# E-Reader_v110.net
KiCad netlist of a schematic drawn in EAGLE
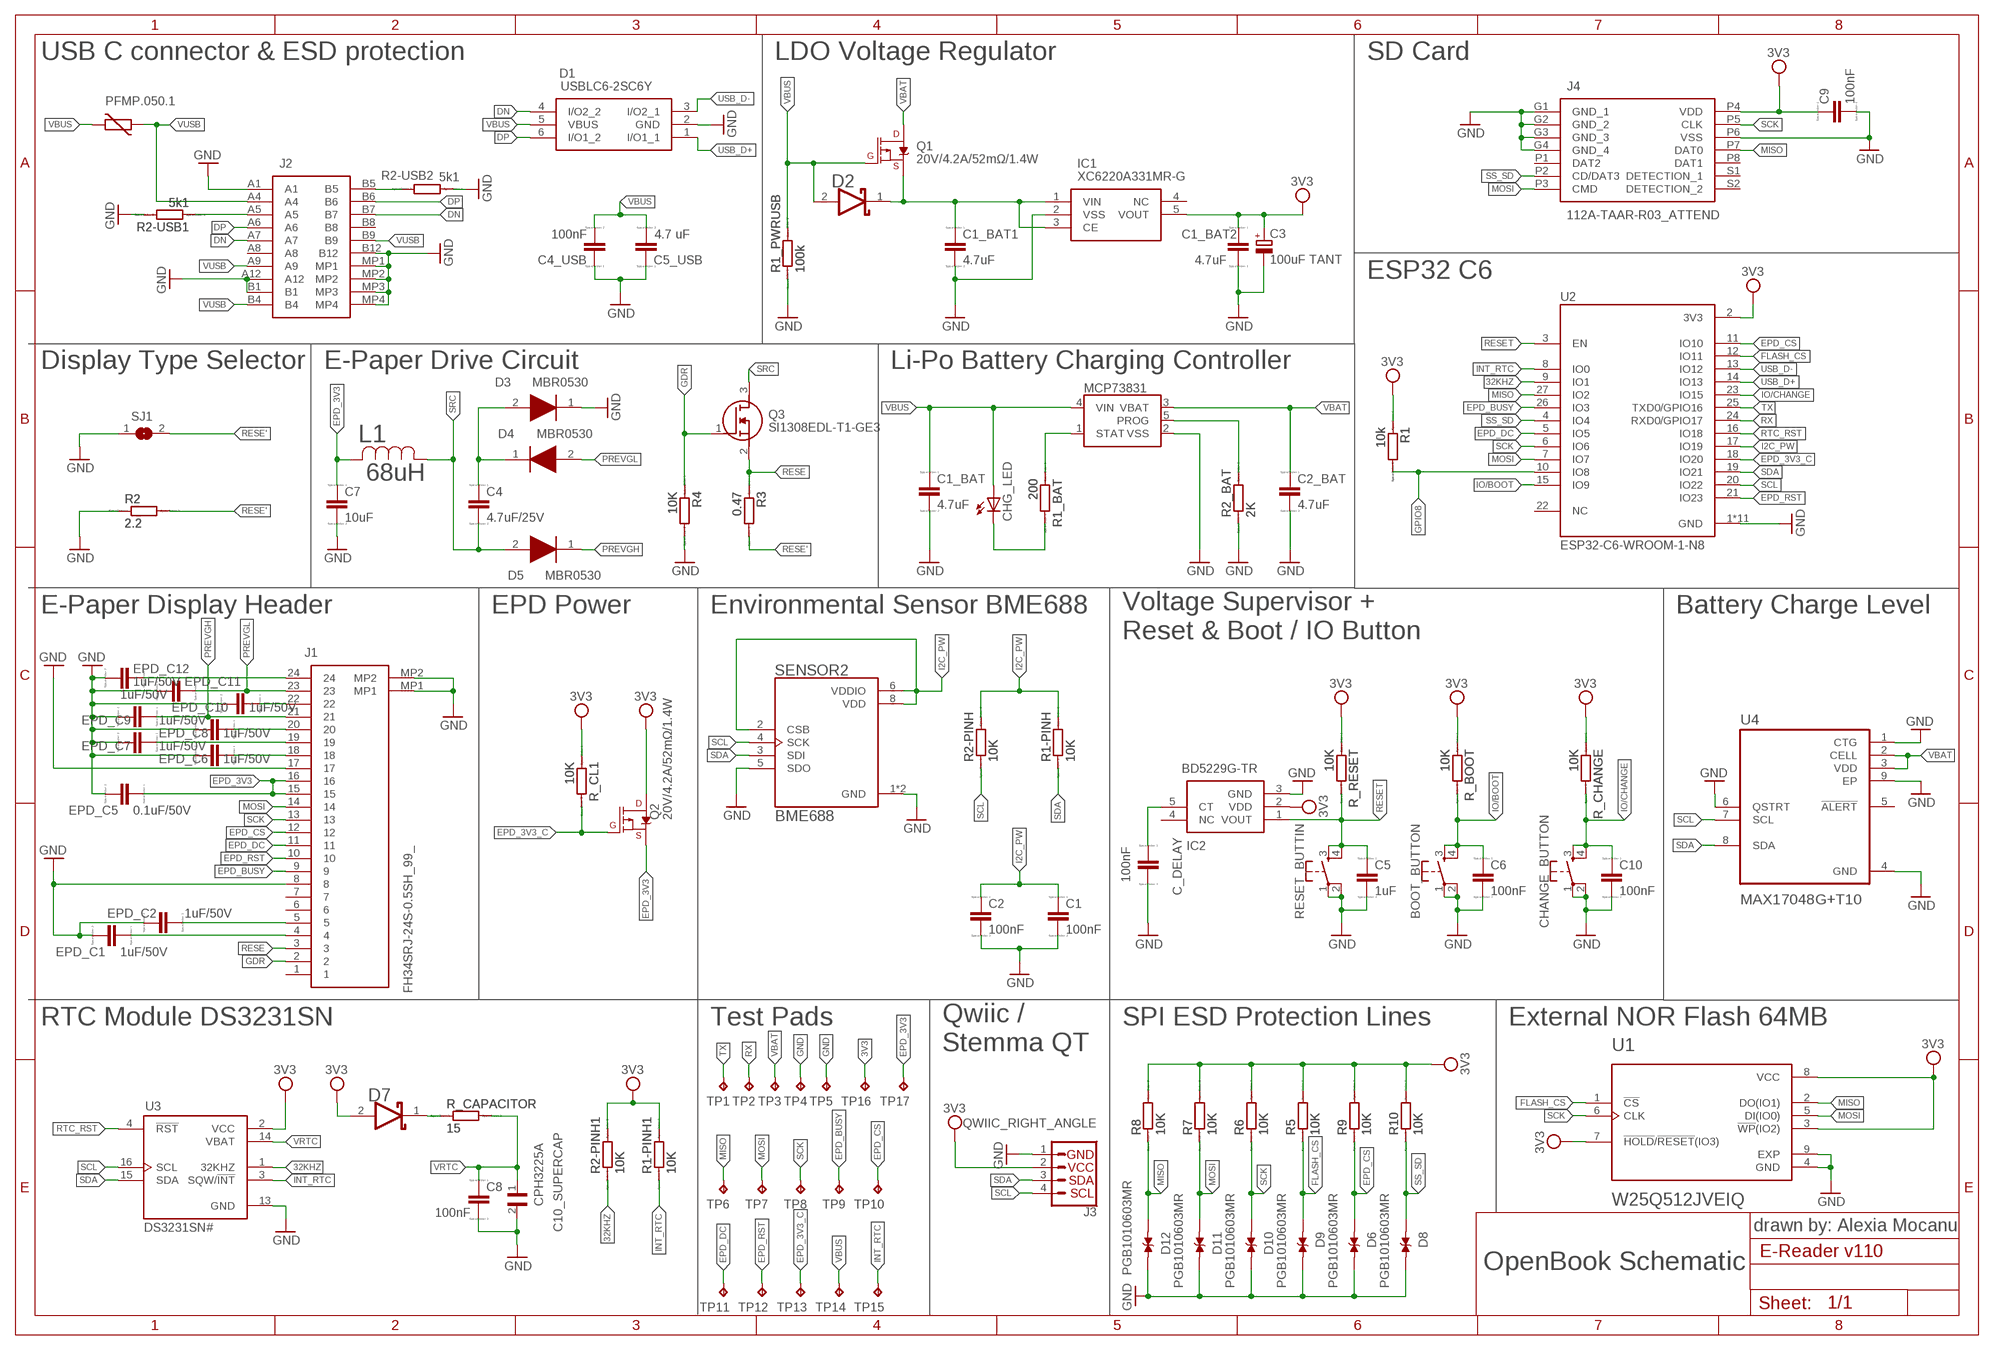
[diagram p0: schematic, sheet 1]

(export (version "E")
  (design (tool "Eeschema 10.0.6"))
  (components
    (comp (ref "BOOT_BUTTON")
      (value "BUTTON_CUSYOMV1")
      (footprint "eagle-import:MYBUTTON")
      (libsource (lib "eagle-import") (part "BUTTON_CUSYOMV1"))
    )
    (comp (ref "C1")
      (value "100nF")
      (footprint "eagle-import:EAGLE-LTSPICE_C0402")
      (libsource (lib "eagle-import") (part "EAGLE-LTSPICE_CC0402"))
    )
    (comp (ref "C1_BAT")
      (value "4.7uF")
      (footprint "eagle-import:EAGLE-LTSPICE_C0402")
      (libsource (lib "eagle-import") (part "EAGLE-LTSPICE_CC0402"))
    )
    (comp (ref "C1_BAT1")
      (value "4.7uF")
      (footprint "eagle-import:EAGLE-LTSPICE_C0402")
      (libsource (lib "eagle-import") (part "EAGLE-LTSPICE_CC0402"))
    )
    (comp (ref "C1_BAT2")
      (value "4.7uF")
      (footprint "eagle-import:EAGLE-LTSPICE_C0402")
      (libsource (lib "eagle-import") (part "EAGLE-LTSPICE_CC0402"))
    )
    (comp (ref "C2")
      (value "100nF")
      (footprint "eagle-import:EAGLE-LTSPICE_C0402")
      (libsource (lib "eagle-import") (part "EAGLE-LTSPICE_CC0402"))
    )
    (comp (ref "C2_BAT")
      (value "4.7uF")
      (footprint "eagle-import:EAGLE-LTSPICE_C0402")
      (libsource (lib "eagle-import") (part "EAGLE-LTSPICE_CC0402"))
    )
    (comp (ref "C3")
      (value "100uF TANT")
      (footprint "eagle-import:RCL_CT3528")
      (libsource (lib "eagle-import") (part "RCL_CPOL-EUCT3528"))
    )
    (comp (ref "C4")
      (value "4.7uF/25V")
      (footprint "eagle-import:EAGLE-LTSPICE_C0402")
      (libsource (lib "eagle-import") (part "EAGLE-LTSPICE_CC0402"))
    )
    (comp (ref "C4_USB")
      (value "100nF")
      (footprint "eagle-import:EAGLE-LTSPICE_C0402")
      (libsource (lib "eagle-import") (part "EAGLE-LTSPICE_CC0402"))
    )
    (comp (ref "C5")
      (value "1uF")
      (footprint "eagle-import:EAGLE-LTSPICE_C0402")
      (libsource (lib "eagle-import") (part "EAGLE-LTSPICE_CC0402"))
    )
    (comp (ref "C5_USB")
      (value "4.7 uF")
      (footprint "eagle-import:EAGLE-LTSPICE_C0402")
      (libsource (lib "eagle-import") (part "EAGLE-LTSPICE_CC0402"))
    )
    (comp (ref "C6")
      (value "100nF")
      (footprint "eagle-import:EAGLE-LTSPICE_C0402")
      (libsource (lib "eagle-import") (part "EAGLE-LTSPICE_CC0402"))
    )
    (comp (ref "C7")
      (value "10uF")
      (footprint "eagle-import:EAGLE-LTSPICE_C0402")
      (libsource (lib "eagle-import") (part "EAGLE-LTSPICE_CC0402"))
    )
    (comp (ref "C8")
      (value "100nF")
      (footprint "eagle-import:EAGLE-LTSPICE_C0402")
      (libsource (lib "eagle-import") (part "EAGLE-LTSPICE_CC0402"))
    )
    (comp (ref "C9")
      (value "100nF")
      (footprint "eagle-import:EAGLE-LTSPICE_C0402")
      (libsource (lib "eagle-import") (part "EAGLE-LTSPICE_CC0402"))
    )
    (comp (ref "C10")
      (value "100nF")
      (footprint "eagle-import:EAGLE-LTSPICE_C0402")
      (libsource (lib "eagle-import") (part "EAGLE-LTSPICE_CC0402"))
    )
    (comp (ref "C10_SUPERCAP")
      (value "CPH3225A")
      (footprint "eagle-import:CAPCP3225X100N")
      (fields (field (name "MF") "Seiko Instruments"))
      (libsource (lib "eagle-import") (part "CPH3225A"))
    )
    (comp (ref "CHANGE_BUTTON")
      (value "BUTTON_CUSYOMV1")
      (footprint "eagle-import:MYBUTTON")
      (libsource (lib "eagle-import") (part "BUTTON_CUSYOMV1"))
    )
    (comp (ref "CHG_LED")
      (value "ADAFRUIT_LEDCHIP-LED0603")
      (footprint "eagle-import:ADAFRUIT_CHIP-LED0603")
      (libsource (lib "eagle-import") (part "ADAFRUIT_LEDCHIP-LED0603"))
    )
    (comp (ref "C_DELAY")
      (value "100nF")
      (footprint "eagle-import:EAGLE-LTSPICE_C0402")
      (libsource (lib "eagle-import") (part "EAGLE-LTSPICE_CC0402"))
    )
    (comp (ref "D1")
      (value "USBLC6-2SC6Y")
      (footprint "eagle-import:SOT95P280X145-6N")
      (fields (field (name "MF") "STMicroelectronics"))
      (libsource (lib "eagle-import") (part "USBLC6-2SC6Y"))
    )
    (comp (ref "D2")
      (value "ESP32_WROVER_AVX---SD0805S020S1R0_AVX_SD0805S020S1R0_0_0AVX_SD0805S020S1R0_0_0")
      (footprint "eagle-import:ESP32_WROVER_AVX---SD0805S020S1R0_AVX_SD0805S020S1R0_0")
      (fields
        (field (name "DIGIKEY_PART_NUMBER") "478-7800-1-ND")
        (field (name "MF") "AVX")
        (field (name "MOUSER_PART_NUMBER") "581-SD0805S020S1R0")
      )
      (libsource (lib "eagle-import") (part "ESP32_WROVER_AVX---SD0805S020S1R0_AVX_SD0805S020S1R0_0_0AVX_SD0805S020S1R0_0_0"))
    )
    (comp (ref "D3")
      (value "MBR0530")
      (footprint "eagle-import:SOD3716X135N")
      (fields (field (name "MF") "ON Semiconductor"))
      (libsource (lib "eagle-import") (part "MBR0530"))
    )
    (comp (ref "D4")
      (value "MBR0530")
      (footprint "eagle-import:SOD3716X135N")
      (fields (field (name "MF") "ON Semiconductor"))
      (libsource (lib "eagle-import") (part "MBR0530"))
    )
    (comp (ref "D5")
      (value "MBR0530")
      (footprint "eagle-import:SOD3716X135N")
      (fields (field (name "MF") "ON Semiconductor"))
      (libsource (lib "eagle-import") (part "MBR0530"))
    )
    (comp (ref "D6")
      (value "PGB1010603MR")
      (footprint "eagle-import:DIOC1608X36N")
      (fields (field (name "MF") "Littelfuse Inc."))
      (libsource (lib "eagle-import") (part "PGB1010603MR"))
    )
    (comp (ref "D7")
      (value "SD0805S020S1R0")
      (footprint "eagle-import:ESP32_WROVER_AVX---SD0805S020S1R0_AVX_SD0805S020S1R0_0")
      (fields
        (field (name "DIGIKEY_PART_NUMBER") "478-7800-1-ND")
        (field (name "MF") "AVX")
        (field (name "MOUSER_PART_NUMBER") "581-SD0805S020S1R0")
      )
      (libsource (lib "eagle-import") (part "ESP32_WROVER_AVX---SD0805S020S1R0_AVX_SD0805S020S1R0_0_0AVX_SD0805S020S1R0_0_0"))
    )
    (comp (ref "D8")
      (value "PGB1010603MR")
      (footprint "eagle-import:DIOC1608X36N")
      (fields (field (name "MF") "Littelfuse Inc."))
      (libsource (lib "eagle-import") (part "PGB1010603MR"))
    )
    (comp (ref "D9")
      (value "PGB1010603MR")
      (footprint "eagle-import:DIOC1608X36N")
      (fields (field (name "MF") "Littelfuse Inc."))
      (libsource (lib "eagle-import") (part "PGB1010603MR"))
    )
    (comp (ref "D10")
      (value "PGB1010603MR")
      (footprint "eagle-import:DIOC1608X36N")
      (fields (field (name "MF") "Littelfuse Inc."))
      (libsource (lib "eagle-import") (part "PGB1010603MR"))
    )
    (comp (ref "D11")
      (value "PGB1010603MR")
      (footprint "eagle-import:DIOC1608X36N")
      (fields (field (name "MF") "Littelfuse Inc."))
      (libsource (lib "eagle-import") (part "PGB1010603MR"))
    )
    (comp (ref "D12")
      (value "PGB1010603MR")
      (footprint "eagle-import:DIOC1608X36N")
      (fields (field (name "MF") "Littelfuse Inc."))
      (libsource (lib "eagle-import") (part "PGB1010603MR"))
    )
    (comp (ref "EPD_C1")
      (value "1uF/50V")
      (footprint "eagle-import:EAGLE-LTSPICE_C0402")
      (libsource (lib "eagle-import") (part "EAGLE-LTSPICE_CC0402"))
    )
    (comp (ref "EPD_C2")
      (value "1uF/50V")
      (footprint "eagle-import:EAGLE-LTSPICE_C0402")
      (libsource (lib "eagle-import") (part "EAGLE-LTSPICE_CC0402"))
    )
    (comp (ref "EPD_C5")
      (value "0.1uF/50V")
      (footprint "eagle-import:EAGLE-LTSPICE_C0402")
      (libsource (lib "eagle-import") (part "EAGLE-LTSPICE_CC0402"))
    )
    (comp (ref "EPD_C6")
      (value "1uF/50V")
      (footprint "eagle-import:EAGLE-LTSPICE_C0402")
      (libsource (lib "eagle-import") (part "EAGLE-LTSPICE_CC0402"))
    )
    (comp (ref "EPD_C7")
      (value "1uF/50V")
      (footprint "eagle-import:EAGLE-LTSPICE_C0402")
      (libsource (lib "eagle-import") (part "EAGLE-LTSPICE_CC0402"))
    )
    (comp (ref "EPD_C8")
      (value "1uF/50V")
      (footprint "eagle-import:EAGLE-LTSPICE_C0402")
      (libsource (lib "eagle-import") (part "EAGLE-LTSPICE_CC0402"))
    )
    (comp (ref "EPD_C9")
      (value "1uF/50V")
      (footprint "eagle-import:EAGLE-LTSPICE_C0402")
      (libsource (lib "eagle-import") (part "EAGLE-LTSPICE_CC0402"))
    )
    (comp (ref "EPD_C10")
      (value "1uF/50V")
      (footprint "eagle-import:EAGLE-LTSPICE_C0402")
      (libsource (lib "eagle-import") (part "EAGLE-LTSPICE_CC0402"))
    )
    (comp (ref "EPD_C11")
      (value "1uF/50V")
      (footprint "eagle-import:EAGLE-LTSPICE_C0402")
      (libsource (lib "eagle-import") (part "EAGLE-LTSPICE_CC0402"))
    )
    (comp (ref "EPD_C12")
      (value "1uF/50V")
      (footprint "eagle-import:EAGLE-LTSPICE_C0402")
      (libsource (lib "eagle-import") (part "EAGLE-LTSPICE_CC0402"))
    )
    (comp (ref "IC1")
      (value "XC6220A331MR-G")
      (footprint "eagle-import:SOT95P280X120-5N")
      (fields (field (name "MOUSER_PART_NUMBER") "865-XC6220A331MR-G"))
      (libsource (lib "eagle-import") (part "XC6220A331MR-G"))
    )
    (comp (ref "IC2")
      (value "BD5229G-TR")
      (footprint "eagle-import:SOT95P280X125-5N")
      (fields (field (name "MOUSER_PART_NUMBER") "755-BD5229G-TR"))
      (libsource (lib "eagle-import") (part "BD5229G-TR"))
    )
    (comp (ref "J1")
      (value "FH34SRJ-24S-0.5SH_99_")
      (footprint "eagle-import:FH34SRJ24S05SH99")
      (fields
        (field (name "MANUFACTURER_PART_NUMBER") "FH34SRJ-24S-0.5SH(99)")
        (field (name "MOUSER_PART_NUMBER") "798-FH34SRJ24S05SH99")
      )
      (libsource (lib "eagle-import") (part "FH34SRJ-24S-0.5SH_99_"))
    )
    (comp (ref "J2")
      (value "SAMACSYS_PARTS_USB4110-GF-A")
      (footprint "eagle-import:SAMACSYS_PARTS_USB4110GFA")
      (fields
        (field (name "MANUFACTURER_PART_NUMBER") "USB4110-GF-A")
        (field (name "MOUSER_PART_NUMBER") "640-USB4110-GF-A")
      )
      (libsource (lib "eagle-import") (part "SAMACSYS_PARTS_USB4110-GF-A"))
    )
    (comp (ref "J3")
      (value "QWIIC_RIGHT_ANGLE")
      (footprint "eagle-import:JST04_1MM_RA")
      (libsource (lib "eagle-import") (part "QWIIC_CONNECTORJS-1MM"))
    )
    (comp (ref "J4")
      (value "112A-TAAR-R03_ATTEND")
      (footprint "eagle-import:112ATAARR03ATTEND")
      (fields (field (name "MANUFACTURER_PART_NUMBER") "112A-TAAR-R03 ATTEND"))
      (libsource (lib "eagle-import") (part "112A-TAAR-R03_ATTEND"))
    )
    (comp (ref "L1")
      (value "68uH")
      (footprint "eagle-import:IND_4828-WE-TPC_WRE")
      (fields
        (field (name "MANUFACTURER_PART_NUMBER") "744043680")
        (field (name "COPYRIGHT") "Copyright (C) 2024 Ultra Librarian. All rights reserved.")
      )
      (libsource (lib "eagle-import") (part "744043680IND_4828-WE-TPC_WRE"))
    )
    (comp (ref "MCP73831")
      (value "ESP32_WROVER_SPARKFUN-IC-POWER_MCP73831")
      (footprint "eagle-import:ESP32_WROVER_SPARKFUN-IC-POWER_SOT23-5")
      (libsource (lib "eagle-import") (part "ESP32_WROVER_SPARKFUN-IC-POWER_MCP73831"))
    )
    (comp (ref "PFMP.050.1")
      (value "ESP32C6_VARISTORCN1812")
      (footprint "eagle-import:ESP32C6_VARISTOR_CT_CN1812")
      (libsource (lib "eagle-import") (part "ESP32C6_VARISTORCN1812"))
    )
    (comp (ref "Q1")
      (value "20V/4.2A/52mΩ/1.4W")
      (footprint "eagle-import:ESP32_WROVER_SPARKFUN-DISCRETESEMI_SOT23-3")
      (libsource (lib "eagle-import") (part "ESP32_WROVER_SPARKFUN-DISCRETESEMI_MOSFET_PCH-DMG2305UX-7"))
    )
    (comp (ref "Q2")
      (value "20V/4.2A/52mΩ/1.4W")
      (footprint "eagle-import:ESP32_WROVER_SPARKFUN-DISCRETESEMI_SOT23-3")
      (fields (field (name "SPICEPREFIX") "Q"))
      (libsource (lib "eagle-import") (part "ESP32_WROVER_SPARKFUN-DISCRETESEMI_MOSFET_PCH-DMG2305UX-7"))
    )
    (comp (ref "Q3")
      (value "SI1308EDL-T1-GE3")
      (footprint "eagle-import:SOT65P210X110-3N")
      (fields (field (name "MF") "Vishay Siliconix"))
      (libsource (lib "eagle-import") (part "SI1308EDL-T1-GE3"))
    )
    (comp (ref "R1")
      (value "10k")
      (footprint "eagle-import:ESP32_WROVER_EAGLE-LTSPICE_R0402")
      (libsource (lib "eagle-import") (part "ESP32_WROVER_EAGLE-LTSPICE_RR0402"))
    )
    (comp (ref "R1-PINH")
      (value "10K")
      (footprint "eagle-import:ESP32_WROVER_EAGLE-LTSPICE_R0402")
      (libsource (lib "eagle-import") (part "ESP32_WROVER_EAGLE-LTSPICE_RR0402"))
    )
    (comp (ref "R1-PINH1")
      (value "10K")
      (footprint "eagle-import:ESP32_WROVER_EAGLE-LTSPICE_R0402")
      (libsource (lib "eagle-import") (part "ESP32_WROVER_EAGLE-LTSPICE_RR0402"))
    )
    (comp (ref "R1_BAT")
      (value "200")
      (footprint "eagle-import:ESP32_WROVER_EAGLE-LTSPICE_R0402")
      (libsource (lib "eagle-import") (part "ESP32_WROVER_EAGLE-LTSPICE_RR0402"))
    )
    (comp (ref "R1_PWRUSB")
      (value "100k")
      (footprint "eagle-import:ESP32_WROVER_EAGLE-LTSPICE_R0402")
      (libsource (lib "eagle-import") (part "ESP32_WROVER_EAGLE-LTSPICE_RR0402"))
    )
    (comp (ref "R2")
      (value "2.2")
      (footprint "eagle-import:ESP32_WROVER_EAGLE-LTSPICE_R0402")
      (libsource (lib "eagle-import") (part "ESP32_WROVER_EAGLE-LTSPICE_RR0402"))
    )
    (comp (ref "R2-PINH")
      (value "10K")
      (footprint "eagle-import:ESP32_WROVER_EAGLE-LTSPICE_R0402")
      (libsource (lib "eagle-import") (part "ESP32_WROVER_EAGLE-LTSPICE_RR0402"))
    )
    (comp (ref "R2-PINH1")
      (value "10K")
      (footprint "eagle-import:ESP32_WROVER_EAGLE-LTSPICE_R0402")
      (libsource (lib "eagle-import") (part "ESP32_WROVER_EAGLE-LTSPICE_RR0402"))
    )
    (comp (ref "R2-USB1")
      (value "5k1")
      (footprint "eagle-import:ESP32_WROVER_EAGLE-LTSPICE_R0402")
      (libsource (lib "eagle-import") (part "ESP32_WROVER_EAGLE-LTSPICE_RR0402"))
    )
    (comp (ref "R2-USB2")
      (value "5k1")
      (footprint "eagle-import:ESP32_WROVER_EAGLE-LTSPICE_R0402")
      (libsource (lib "eagle-import") (part "ESP32_WROVER_EAGLE-LTSPICE_RR0402"))
    )
    (comp (ref "R2_BAT")
      (value "2K")
      (footprint "eagle-import:ESP32_WROVER_EAGLE-LTSPICE_R0402")
      (libsource (lib "eagle-import") (part "ESP32_WROVER_EAGLE-LTSPICE_RR0402"))
    )
    (comp (ref "R3")
      (value "0.47")
      (footprint "eagle-import:ESP32_WROVER_EAGLE-LTSPICE_R0402")
      (libsource (lib "eagle-import") (part "ESP32_WROVER_EAGLE-LTSPICE_RR0402"))
    )
    (comp (ref "R4")
      (value "10K")
      (footprint "eagle-import:ESP32_WROVER_EAGLE-LTSPICE_R0402")
      (libsource (lib "eagle-import") (part "ESP32_WROVER_EAGLE-LTSPICE_RR0402"))
    )
    (comp (ref "R5")
      (value "10K")
      (footprint "eagle-import:ESP32_WROVER_EAGLE-LTSPICE_R0402")
      (libsource (lib "eagle-import") (part "ESP32_WROVER_EAGLE-LTSPICE_RR0402"))
    )
    (comp (ref "R6")
      (value "10K")
      (footprint "eagle-import:ESP32_WROVER_EAGLE-LTSPICE_R0402")
      (libsource (lib "eagle-import") (part "ESP32_WROVER_EAGLE-LTSPICE_RR0402"))
    )
    (comp (ref "R7")
      (value "10K")
      (footprint "eagle-import:ESP32_WROVER_EAGLE-LTSPICE_R0402")
      (libsource (lib "eagle-import") (part "ESP32_WROVER_EAGLE-LTSPICE_RR0402"))
    )
    (comp (ref "R8")
      (value "10K")
      (footprint "eagle-import:ESP32_WROVER_EAGLE-LTSPICE_R0402")
      (libsource (lib "eagle-import") (part "ESP32_WROVER_EAGLE-LTSPICE_RR0402"))
    )
    (comp (ref "R9")
      (value "10K")
      (footprint "eagle-import:ESP32_WROVER_EAGLE-LTSPICE_R0402")
      (libsource (lib "eagle-import") (part "ESP32_WROVER_EAGLE-LTSPICE_RR0402"))
    )
    (comp (ref "R10")
      (value "10K")
      (footprint "eagle-import:ESP32_WROVER_EAGLE-LTSPICE_R0402")
      (libsource (lib "eagle-import") (part "ESP32_WROVER_EAGLE-LTSPICE_RR0402"))
    )
    (comp (ref "RESET_BUTTIN")
      (value "BUTTON_CUSYOMV1")
      (footprint "eagle-import:MYBUTTON")
      (libsource (lib "eagle-import") (part "BUTTON_CUSYOMV1"))
    )
    (comp (ref "R_BOOT")
      (value "10K")
      (footprint "eagle-import:ESP32_WROVER_EAGLE-LTSPICE_R0402")
      (libsource (lib "eagle-import") (part "ESP32_WROVER_EAGLE-LTSPICE_RR0402"))
    )
    (comp (ref "R_CAPACITOR")
      (value "15")
      (footprint "eagle-import:ESP32_WROVER_EAGLE-LTSPICE_R0402")
      (libsource (lib "eagle-import") (part "ESP32_WROVER_EAGLE-LTSPICE_RR0402"))
    )
    (comp (ref "R_CHANGE")
      (value "10K")
      (footprint "eagle-import:ESP32_WROVER_EAGLE-LTSPICE_R0402")
      (libsource (lib "eagle-import") (part "ESP32_WROVER_EAGLE-LTSPICE_RR0402"))
    )
    (comp (ref "R_CL1")
      (value "10K")
      (footprint "eagle-import:ESP32_WROVER_EAGLE-LTSPICE_R0402")
      (libsource (lib "eagle-import") (part "ESP32_WROVER_EAGLE-LTSPICE_RR0402"))
    )
    (comp (ref "R_RESET")
      (value "10K")
      (footprint "eagle-import:ESP32_WROVER_EAGLE-LTSPICE_R0402")
      (libsource (lib "eagle-import") (part "ESP32_WROVER_EAGLE-LTSPICE_RR0402"))
    )
    (comp (ref "SENSOR2")
      (value "BME688")
      (footprint "eagle-import:ESP32_WROVER_BME680_PSON80P300X300X100-8N")
      (fields (field (name "MF") "Bosch Sensortec") (field (name "MP") "BME680"))
      (libsource (lib "eagle-import") (part "ESP32_WROVER_BME680_BME680"))
    )
    (comp (ref "SJ1") (value "SJ") (footprint "eagle-import:SJ") (libsource (lib "eagle-import") (part "SJ")))
    (comp (ref "TP1")
      (value "TPTP20R")
      (footprint "eagle-import:TP20R")
      (libsource (lib "eagle-import") (part "TPTP20R"))
    )
    (comp (ref "TP2")
      (value "TPTP20R")
      (footprint "eagle-import:TP20R")
      (libsource (lib "eagle-import") (part "TPTP20R"))
    )
    (comp (ref "TP3")
      (value "TPTP20R")
      (footprint "eagle-import:TP20R")
      (libsource (lib "eagle-import") (part "TPTP20R"))
    )
    (comp (ref "TP4")
      (value "TPTP20R")
      (footprint "eagle-import:TP20R")
      (libsource (lib "eagle-import") (part "TPTP20R"))
    )
    (comp (ref "TP5")
      (value "TPTP20R")
      (footprint "eagle-import:TP20R")
      (libsource (lib "eagle-import") (part "TPTP20R"))
    )
    (comp (ref "TP6")
      (value "TPTP20R")
      (footprint "eagle-import:TP20R")
      (libsource (lib "eagle-import") (part "TPTP20R"))
    )
    (comp (ref "TP7")
      (value "TPTP20R")
      (footprint "eagle-import:TP20R")
      (libsource (lib "eagle-import") (part "TPTP20R"))
    )
    (comp (ref "TP8")
      (value "TPTP20R")
      (footprint "eagle-import:TP20R")
      (libsource (lib "eagle-import") (part "TPTP20R"))
    )
    (comp (ref "TP9")
      (value "TPTP20R")
      (footprint "eagle-import:TP20R")
      (libsource (lib "eagle-import") (part "TPTP20R"))
    )
    (comp (ref "TP10")
      (value "TPTP20R")
      (footprint "eagle-import:TP20R")
      (libsource (lib "eagle-import") (part "TPTP20R"))
    )
    (comp (ref "TP11")
      (value "TPTP20R")
      (footprint "eagle-import:TP20R")
      (libsource (lib "eagle-import") (part "TPTP20R"))
    )
    (comp (ref "TP12")
      (value "TPTP20R")
      (footprint "eagle-import:TP20R")
      (libsource (lib "eagle-import") (part "TPTP20R"))
    )
    (comp (ref "TP13")
      (value "TPTP20R")
      (footprint "eagle-import:TP20R")
      (libsource (lib "eagle-import") (part "TPTP20R"))
    )
    (comp (ref "TP14")
      (value "TPTP20R")
      (footprint "eagle-import:TP20R")
      (libsource (lib "eagle-import") (part "TPTP20R"))
    )
    (comp (ref "TP15")
      (value "TPTP20R")
      (footprint "eagle-import:TP20R")
      (libsource (lib "eagle-import") (part "TPTP20R"))
    )
    (comp (ref "TP16")
      (value "TPTP20R")
      (footprint "eagle-import:TP20R")
      (libsource (lib "eagle-import") (part "TPTP20R"))
    )
    (comp (ref "TP17")
      (value "TPTP20R")
      (footprint "eagle-import:TP20R")
      (libsource (lib "eagle-import") (part "TPTP20R"))
    )
    (comp (ref "U1")
      (value "W25Q512JVEIQ")
      (footprint "eagle-import:SON127P600X800X80-9N")
      (fields (field (name "MF") "Winbond Electronics"))
      (libsource (lib "eagle-import") (part "W25Q512JVEIQ"))
    )
    (comp (ref "U2")
      (value "ESP32-C6-WROOM-1-N8")
      (footprint "eagle-import:XCVR_ESP32-C6-WROOM-1-N8")
      (fields (field (name "MF") "Espressif Systems"))
      (libsource (lib "eagle-import") (part "ESP32-C6-WROOM-1-N8"))
    )
    (comp (ref "U3")
      (value "DS3231SN#")
      (footprint "eagle-import:SOIC127P1032X265-16N")
      (fields (field (name "MF") "Analog Devices"))
      (libsource (lib "eagle-import") (part "DS3231SN#"))
    )
    (comp (ref "U4")
      (value "MAX17048G+T10")
      (footprint "eagle-import:SON50P200X200X80-9N")
      (fields (field (name "MF") "Analog Devices"))
      (libsource (lib "eagle-import") (part "MAX17048G+T10"))
    )
  )
  (nets
    (net (code "1") (name "3V3") (class "Default")
      (node (ref "C1_BAT2") (pin "1") (pinfunction "1_1") (pintype "passive"))
      (node (ref "C3") (pin "+") (pinfunction "+_+") (pintype "passive"))
      (node (ref "C9") (pin "1") (pinfunction "1_1") (pintype "passive"))
      (node (ref "D7") (pin "2") (pinfunction "ANODE_2") (pintype "bidirectional"))
      (node (ref "IC1") (pin "5") (pinfunction "VOUT_5") (pintype "bidirectional"))
      (node (ref "IC2") (pin "2") (pinfunction "VDD_2") (pintype "bidirectional"))
      (node (ref "J3") (pin "2") (pinfunction "2_2") (pintype "power_in"))
      (node (ref "J4") (pin "P4") (pinfunction "VDD_P4") (pintype "bidirectional"))
      (node (ref "Q2") (pin "3") (pinfunction "D_3") (pintype "bidirectional"))
      (node (ref "R1") (pin "1") (pinfunction "1_1") (pintype "passive"))
      (node (ref "R1-PINH1") (pin "2") (pinfunction "2_2") (pintype "passive"))
      (node (ref "R10") (pin "2") (pinfunction "2_2") (pintype "passive"))
      (node (ref "R2-PINH1") (pin "2") (pinfunction "2_2") (pintype "passive"))
      (node (ref "R5") (pin "2") (pinfunction "2_2") (pintype "passive"))
      (node (ref "R6") (pin "2") (pinfunction "2_2") (pintype "passive"))
      (node (ref "R7") (pin "2") (pinfunction "2_2") (pintype "passive"))
      (node (ref "R8") (pin "2") (pinfunction "2_2") (pintype "passive"))
      (node (ref "R9") (pin "2") (pinfunction "2_2") (pintype "passive"))
      (node (ref "R_BOOT") (pin "1") (pinfunction "1_1") (pintype "passive"))
      (node (ref "R_CHANGE") (pin "1") (pinfunction "1_1") (pintype "passive"))
      (node (ref "R_CL1") (pin "1") (pinfunction "1_1") (pintype "passive"))
      (node (ref "R_RESET") (pin "1") (pinfunction "1_1") (pintype "passive"))
      (node (ref "TP16") (pin "TP") (pinfunction "TP_TP") (pintype "input"))
      (node (ref "U1") (pin "3") (pinfunction "~{WP}(IO2)_3") (pintype "bidirectional"))
      (node (ref "U1") (pin "7") (pinfunction "~{HOLD}/~{RESET}(IO3)_7") (pintype "bidirectional"))
      (node (ref "U1") (pin "8") (pinfunction "VCC_8") (pintype "power_in"))
      (node (ref "U2") (pin "2") (pinfunction "3V3_2") (pintype "power_in"))
      (node (ref "U3") (pin "2") (pinfunction "VCC_2") (pintype "power_in"))
    )
    (net (code "2") (name "32KHZ") (class "Default")
      (node (ref "R2-PINH1") (pin "1") (pinfunction "1_1") (pintype "passive"))
      (node (ref "U2") (pin "9") (pinfunction "IO1_9") (pintype "bidirectional"))
      (node (ref "U3") (pin "1") (pinfunction "32KHZ_1") (pintype "output"))
    )
    (net (code "3") (name "DN") (class "Default")
      (node (ref "D1") (pin "4") (pinfunction "I/O2_2_4") (pintype "bidirectional"))
      (node (ref "J2") (pin "A7") (pinfunction "A7_A7") (pintype "bidirectional"))
      (node (ref "J2") (pin "B7") (pinfunction "B7_B7") (pintype "bidirectional"))
    )
    (net (code "4") (name "DP") (class "Default")
      (node (ref "D1") (pin "6") (pinfunction "I/O1_2_6") (pintype "bidirectional"))
      (node (ref "J2") (pin "A6") (pinfunction "A6_A6") (pintype "bidirectional"))
      (node (ref "J2") (pin "B6") (pinfunction "B6_B6") (pintype "bidirectional"))
    )
    (net (code "5") (name "EPD_3V3") (class "Default")
      (node (ref "C7") (pin "1") (pinfunction "1_1") (pintype "passive"))
      (node (ref "EPD_C5") (pin "1") (pinfunction "1_1") (pintype "passive"))
      (node (ref "J1") (pin "15") (pinfunction "15_15") (pintype "bidirectional"))
      (node (ref "J1") (pin "16") (pinfunction "16_16") (pintype "bidirectional"))
      (node (ref "L1") (pin "2") (pinfunction "2_2") (pintype "passive"))
      (node (ref "Q2") (pin "2") (pinfunction "S_2") (pintype "bidirectional"))
      (node (ref "TP17") (pin "TP") (pinfunction "TP_TP") (pintype "input"))
    )
    (net (code "6") (name "EPD_3V3_C") (class "Default")
      (node (ref "Q2") (pin "1") (pinfunction "G_1") (pintype "bidirectional"))
      (node (ref "R_CL1") (pin "2") (pinfunction "2_2") (pintype "passive"))
      (node (ref "TP13") (pin "TP") (pinfunction "TP_TP") (pintype "input"))
      (node (ref "U2") (pin "18") (pinfunction "IO20_18") (pintype "bidirectional"))
    )
    (net (code "7") (name "EPD_BUSY") (class "Default")
      (node (ref "J1") (pin "9") (pinfunction "9_9") (pintype "bidirectional"))
      (node (ref "TP9") (pin "TP") (pinfunction "TP_TP") (pintype "input"))
      (node (ref "U2") (pin "26") (pinfunction "IO3_26") (pintype "bidirectional"))
    )
    (net (code "8") (name "EPD_CS") (class "Default")
      (node (ref "D6") (pin "1") (pinfunction "1_1") (pintype "passive"))
      (node (ref "J1") (pin "12") (pinfunction "12_12") (pintype "bidirectional"))
      (node (ref "R9") (pin "1") (pinfunction "1_1") (pintype "passive"))
      (node (ref "TP10") (pin "TP") (pinfunction "TP_TP") (pintype "input"))
      (node (ref "U2") (pin "11") (pinfunction "IO10_11") (pintype "bidirectional"))
    )
    (net (code "9") (name "EPD_DC") (class "Default")
      (node (ref "J1") (pin "11") (pinfunction "11_11") (pintype "bidirectional"))
      (node (ref "TP11") (pin "TP") (pinfunction "TP_TP") (pintype "input"))
      (node (ref "U2") (pin "5") (pinfunction "IO5_5") (pintype "bidirectional"))
    )
    (net (code "10") (name "EPD_RST") (class "Default")
      (node (ref "J1") (pin "10") (pinfunction "10_10") (pintype "bidirectional"))
      (node (ref "TP12") (pin "TP") (pinfunction "TP_TP") (pintype "input"))
      (node (ref "U2") (pin "21") (pinfunction "IO23_21") (pintype "bidirectional"))
    )
    (net (code "11") (name "FLASH_CS") (class "Default")
      (node (ref "D9") (pin "1") (pinfunction "1_1") (pintype "passive"))
      (node (ref "R5") (pin "1") (pinfunction "1_1") (pintype "passive"))
      (node (ref "U1") (pin "1") (pinfunction "~{CS}_1") (pintype "input"))
      (node (ref "U2") (pin "12") (pinfunction "IO11_12") (pintype "bidirectional"))
    )
    (net (code "12") (name "GDR") (class "Default")
      (node (ref "J1") (pin "2") (pinfunction "2_2") (pintype "bidirectional"))
      (node (ref "Q3") (pin "1") (pinfunction "G_1") (pintype "bidirectional"))
      (node (ref "R4") (pin "1") (pinfunction "1_1") (pintype "passive"))
    )
    (net (code "13") (name "GND") (class "Default")
      (node (ref "BOOT_BUTTON") (pin "1") (pinfunction "1_1") (pintype "passive"))
      (node (ref "BOOT_BUTTON") (pin "2") (pinfunction "2_2") (pintype "passive"))
      (node (ref "C1") (pin "2") (pinfunction "2_2") (pintype "passive"))
      (node (ref "C10") (pin "2") (pinfunction "2_2") (pintype "passive"))
      (node (ref "C10_SUPERCAP") (pin "2") (pinfunction "2_2") (pintype "passive"))
      (node (ref "C1_BAT") (pin "2") (pinfunction "2_2") (pintype "passive"))
      (node (ref "C1_BAT1") (pin "2") (pinfunction "2_2") (pintype "passive"))
      (node (ref "C1_BAT2") (pin "2") (pinfunction "2_2") (pintype "passive"))
      (node (ref "C2") (pin "2") (pinfunction "2_2") (pintype "passive"))
      (node (ref "C2_BAT") (pin "2") (pinfunction "2_2") (pintype "passive"))
      (node (ref "C3") (pin "-") (pinfunction "-_-") (pintype "passive"))
      (node (ref "C4_USB") (pin "1") (pinfunction "1_1") (pintype "passive"))
      (node (ref "C5") (pin "2") (pinfunction "2_2") (pintype "passive"))
      (node (ref "C5_USB") (pin "1") (pinfunction "1_1") (pintype "passive"))
      (node (ref "C6") (pin "2") (pinfunction "2_2") (pintype "passive"))
      (node (ref "C7") (pin "2") (pinfunction "2_2") (pintype "passive"))
      (node (ref "C8") (pin "2") (pinfunction "2_2") (pintype "passive"))
      (node (ref "C9") (pin "2") (pinfunction "2_2") (pintype "passive"))
      (node (ref "CHANGE_BUTTON") (pin "1") (pinfunction "1_1") (pintype "passive"))
      (node (ref "CHANGE_BUTTON") (pin "2") (pinfunction "2_2") (pintype "passive"))
      (node (ref "C_DELAY") (pin "2") (pinfunction "2_2") (pintype "passive"))
      (node (ref "D1") (pin "2") (pinfunction "GND_2") (pintype "bidirectional"))
      (node (ref "D10") (pin "2") (pinfunction "2_2") (pintype "passive"))
      (node (ref "D11") (pin "2") (pinfunction "2_2") (pintype "passive"))
      (node (ref "D12") (pin "2") (pinfunction "2_2") (pintype "passive"))
      (node (ref "D3") (pin "1") (pinfunction "K_1") (pintype "bidirectional"))
      (node (ref "D6") (pin "2") (pinfunction "2_2") (pintype "passive"))
      (node (ref "D8") (pin "2") (pinfunction "2_2") (pintype "passive"))
      (node (ref "D9") (pin "2") (pinfunction "2_2") (pintype "passive"))
      (node (ref "EPD_C1") (pin "2") (pinfunction "2_2") (pintype "passive"))
      (node (ref "EPD_C10") (pin "2") (pinfunction "2_2") (pintype "passive"))
      (node (ref "EPD_C11") (pin "2") (pinfunction "2_2") (pintype "passive"))
      (node (ref "EPD_C12") (pin "2") (pinfunction "2_2") (pintype "passive"))
      (node (ref "EPD_C2") (pin "2") (pinfunction "2_2") (pintype "passive"))
      (node (ref "EPD_C5") (pin "2") (pinfunction "2_2") (pintype "passive"))
      (node (ref "EPD_C6") (pin "2") (pinfunction "2_2") (pintype "passive"))
      (node (ref "EPD_C7") (pin "2") (pinfunction "2_2") (pintype "passive"))
      (node (ref "EPD_C8") (pin "2") (pinfunction "2_2") (pintype "passive"))
      (node (ref "EPD_C9") (pin "2") (pinfunction "2_2") (pintype "passive"))
      (node (ref "IC1") (pin "2") (pinfunction "VSS_2") (pintype "bidirectional"))
      (node (ref "IC2") (pin "3") (pinfunction "GND_3") (pintype "bidirectional"))
      (node (ref "J1") (pin "17") (pinfunction "17_17") (pintype "bidirectional"))
      (node (ref "J1") (pin "8") (pinfunction "8_8") (pintype "bidirectional"))
      (node (ref "J1") (pin "MP1") (pinfunction "MP1_MP1") (pintype "bidirectional"))
      (node (ref "J1") (pin "MP2") (pinfunction "MP2_MP2") (pintype "bidirectional"))
      (node (ref "J2") (pin "A1") (pinfunction "A1_A1") (pintype "bidirectional"))
      (node (ref "J2") (pin "A12") (pinfunction "A12_A12") (pintype "bidirectional"))
      (node (ref "J2") (pin "B1") (pinfunction "B1_B1") (pintype "bidirectional"))
      (node (ref "J2") (pin "B12") (pinfunction "B12_B12") (pintype "bidirectional"))
      (node (ref "J2") (pin "MP1") (pinfunction "MP1_MP1") (pintype "bidirectional"))
      (node (ref "J2") (pin "MP2") (pinfunction "MP2_MP2") (pintype "bidirectional"))
      (node (ref "J2") (pin "MP3") (pinfunction "MP3_MP3") (pintype "bidirectional"))
      (node (ref "J2") (pin "MP4") (pinfunction "MP4_MP4") (pintype "bidirectional"))
      (node (ref "J3") (pin "1") (pinfunction "1_1") (pintype "power_in"))
      (node (ref "J4") (pin "G1") (pinfunction "GND_1_G1") (pintype "bidirectional"))
      (node (ref "J4") (pin "G2") (pinfunction "GND_2_G2") (pintype "bidirectional"))
      (node (ref "J4") (pin "G3") (pinfunction "GND_3_G3") (pintype "bidirectional"))
      (node (ref "J4") (pin "G4") (pinfunction "GND_4_G4") (pintype "bidirectional"))
      (node (ref "J4") (pin "P6") (pinfunction "VSS_P6") (pintype "bidirectional"))
      (node (ref "MCP73831") (pin "2") (pinfunction "VSS_2") (pintype "power_in"))
      (node (ref "R1_PWRUSB") (pin "1") (pinfunction "1_1") (pintype "passive"))
      (node (ref "R2") (pin "1") (pinfunction "1_1") (pintype "passive"))
      (node (ref "R2-USB1") (pin "2") (pinfunction "2_2") (pintype "passive"))
      (node (ref "R2-USB2") (pin "1") (pinfunction "1_1") (pintype "passive"))
      (node (ref "R2_BAT") (pin "1") (pinfunction "1_1") (pintype "passive"))
      (node (ref "R4") (pin "2") (pinfunction "2_2") (pintype "passive"))
      (node (ref "RESET_BUTTIN") (pin "1") (pinfunction "1_1") (pintype "passive"))
      (node (ref "RESET_BUTTIN") (pin "2") (pinfunction "2_2") (pintype "passive"))
      (node (ref "SENSOR2") (pin "1") (pinfunction "GND_1") (pintype "power_in"))
      (node (ref "SENSOR2") (pin "5") (pinfunction "SDO_5") (pintype "bidirectional"))
      (node (ref "SENSOR2") (pin "7") (pinfunction "GND_7") (pintype "power_in"))
      (node (ref "SJ1") (pin "1") (pinfunction "1_1") (pintype "passive"))
      (node (ref "TP4") (pin "TP") (pinfunction "TP_TP") (pintype "input"))
      (node (ref "TP5") (pin "TP") (pinfunction "TP_TP") (pintype "input"))
      (node (ref "U1") (pin "4") (pinfunction "GND_4") (pintype "power_in"))
      (node (ref "U1") (pin "9") (pinfunction "EXP_9") (pintype "passive"))
      (node (ref "U2") (pin "1") (pinfunction "GND_1") (pintype "power_in"))
      (node (ref "U2") (pin "28") (pinfunction "GND_28") (pintype "power_in"))
      (node (ref "U2") (pin "29_1") (pinfunction "GND_29_1") (pintype "power_in"))
      (node (ref "U2") (pin "29_2") (pinfunction "GND_29_2") (pintype "power_in"))
      (node (ref "U2") (pin "29_3") (pinfunction "GND_29_3") (pintype "power_in"))
      (node (ref "U2") (pin "29_4") (pinfunction "GND_29_4") (pintype "power_in"))
      (node (ref "U2") (pin "29_5") (pinfunction "GND_29_5") (pintype "power_in"))
      (node (ref "U2") (pin "29_6") (pinfunction "GND_29_6") (pintype "power_in"))
      (node (ref "U2") (pin "29_7") (pinfunction "GND_29_7") (pintype "power_in"))
      (node (ref "U2") (pin "29_8") (pinfunction "GND_29_8") (pintype "power_in"))
      (node (ref "U2") (pin "29_9") (pinfunction "GND_29_9") (pintype "power_in"))
      (node (ref "U3") (pin "13") (pinfunction "GND_13") (pintype "power_in"))
      (node (ref "U4") (pin "1") (pinfunction "CTG_1") (pintype "power_in"))
      (node (ref "U4") (pin "4") (pinfunction "GND_4") (pintype "power_in"))
      (node (ref "U4") (pin "6") (pinfunction "QSTRT_6") (pintype "input"))
      (node (ref "U4") (pin "9") (pinfunction "EP_9") (pintype "power_in"))
    )
    (net (code "14") (name "GPIO8") (class "Default")
      (node (ref "R1") (pin "2") (pinfunction "2_2") (pintype "passive"))
      (node (ref "U2") (pin "10") (pinfunction "IO8_10") (pintype "bidirectional"))
    )
    (net (code "15") (name "I2C_PW") (class "Default")
      (node (ref "C1") (pin "1") (pinfunction "1_1") (pintype "passive"))
      (node (ref "C2") (pin "1") (pinfunction "1_1") (pintype "passive"))
      (node (ref "R1-PINH") (pin "2") (pinfunction "2_2") (pintype "passive"))
      (node (ref "R2-PINH") (pin "2") (pinfunction "2_2") (pintype "passive"))
      (node (ref "SENSOR2") (pin "2") (pinfunction "CSB_2") (pintype "input"))
      (node (ref "SENSOR2") (pin "6") (pinfunction "VDDIO_6") (pintype "power_in"))
      (node (ref "SENSOR2") (pin "8") (pinfunction "VDD_8") (pintype "power_in"))
      (node (ref "U2") (pin "17") (pinfunction "IO19_17") (pintype "bidirectional"))
    )
    (net (code "16") (name "INT_RTC") (class "Default")
      (node (ref "R1-PINH1") (pin "1") (pinfunction "1_1") (pintype "passive"))
      (node (ref "TP15") (pin "TP") (pinfunction "TP_TP") (pintype "input"))
      (node (ref "U2") (pin "8") (pinfunction "IO0_8") (pintype "bidirectional"))
      (node (ref "U3") (pin "3") (pinfunction "SQW/~{INT}_3") (pintype "output"))
    )
    (net (code "17") (name "IO{slash}BOOT") (class "Default")
      (node (ref "BOOT_BUTTON") (pin "3") (pinfunction "3_3") (pintype "passive"))
      (node (ref "BOOT_BUTTON") (pin "4") (pinfunction "4_4") (pintype "passive"))
      (node (ref "C6") (pin "1") (pinfunction "1_1") (pintype "passive"))
      (node (ref "R_BOOT") (pin "2") (pinfunction "2_2") (pintype "passive"))
      (node (ref "U2") (pin "15") (pinfunction "IO9_15") (pintype "bidirectional"))
    )
    (net (code "18") (name "IO{slash}CHANGE") (class "Default")
      (node (ref "C10") (pin "1") (pinfunction "1_1") (pintype "passive"))
      (node (ref "CHANGE_BUTTON") (pin "3") (pinfunction "3_3") (pintype "passive"))
      (node (ref "CHANGE_BUTTON") (pin "4") (pinfunction "4_4") (pintype "passive"))
      (node (ref "R_CHANGE") (pin "2") (pinfunction "2_2") (pintype "passive"))
      (node (ref "U2") (pin "23") (pinfunction "IO15_23") (pintype "bidirectional"))
    )
    (net (code "19") (name "MISO") (class "Default")
      (node (ref "D12") (pin "1") (pinfunction "1_1") (pintype "passive"))
      (node (ref "J4") (pin "P7") (pinfunction "DAT0_P7") (pintype "bidirectional"))
      (node (ref "R8") (pin "1") (pinfunction "1_1") (pintype "passive"))
      (node (ref "TP6") (pin "TP") (pinfunction "TP_TP") (pintype "input"))
      (node (ref "U1") (pin "2") (pinfunction "DO(IO1)_2") (pintype "bidirectional"))
      (node (ref "U2") (pin "27") (pinfunction "IO2_27") (pintype "bidirectional"))
    )
    (net (code "20") (name "MOSI") (class "Default")
      (node (ref "D11") (pin "1") (pinfunction "1_1") (pintype "passive"))
      (node (ref "J1") (pin "14") (pinfunction "14_14") (pintype "bidirectional"))
      (node (ref "J4") (pin "P3") (pinfunction "CMD_P3") (pintype "bidirectional"))
      (node (ref "R7") (pin "1") (pinfunction "1_1") (pintype "passive"))
      (node (ref "TP7") (pin "TP") (pinfunction "TP_TP") (pintype "input"))
      (node (ref "U1") (pin "5") (pinfunction "DI(IO0)_5") (pintype "bidirectional"))
      (node (ref "U2") (pin "7") (pinfunction "IO7_7") (pintype "bidirectional"))
    )
    (net (code "21") (name "Net-(CHG_LED-PadC)") (class "Default")
      (node (ref "CHG_LED") (pin "C") (pinfunction "C_C") (pintype "passive"))
      (node (ref "R1_BAT") (pin "2") (pinfunction "2_2") (pintype "passive"))
    )
    (net (code "22") (name "Net-(D2-CATHODE)") (class "Default")
      (node (ref "C1_BAT1") (pin "1") (pinfunction "1_1") (pintype "passive"))
      (node (ref "D2") (pin "1") (pinfunction "CATHODE_1") (pintype "bidirectional"))
      (node (ref "IC1") (pin "1") (pinfunction "VIN_1") (pintype "bidirectional"))
      (node (ref "IC1") (pin "3") (pinfunction "CE_3") (pintype "bidirectional"))
      (node (ref "Q1") (pin "2") (pinfunction "S_2") (pintype "bidirectional"))
    )
    (net (code "23") (name "Net-(D3-A)") (class "Default")
      (node (ref "C4") (pin "1") (pinfunction "1_1") (pintype "passive"))
      (node (ref "D3") (pin "2") (pinfunction "A_2") (pintype "bidirectional"))
      (node (ref "D4") (pin "1") (pinfunction "K_1") (pintype "bidirectional"))
    )
    (net (code "24") (name "Net-(D7-CATHODE)") (class "Default")
      (node (ref "D7") (pin "1") (pinfunction "CATHODE_1") (pintype "bidirectional"))
      (node (ref "R_CAPACITOR") (pin "1") (pinfunction "1_1") (pintype "passive"))
    )
    (net (code "25") (name "Net-(EPD_C1-Pad1)") (class "Default")
      (node (ref "EPD_C1") (pin "1") (pinfunction "1_1") (pintype "passive"))
      (node (ref "J1") (pin "4") (pinfunction "4_4") (pintype "bidirectional"))
    )
    (net (code "26") (name "Net-(EPD_C2-Pad1)") (class "Default")
      (node (ref "EPD_C2") (pin "1") (pinfunction "1_1") (pintype "passive"))
      (node (ref "J1") (pin "5") (pinfunction "5_5") (pintype "bidirectional"))
    )
    (net (code "27") (name "Net-(EPD_C6-Pad1)") (class "Default")
      (node (ref "EPD_C6") (pin "1") (pinfunction "1_1") (pintype "passive"))
      (node (ref "J1") (pin "18") (pinfunction "18_18") (pintype "bidirectional"))
    )
    (net (code "28") (name "Net-(EPD_C7-Pad1)") (class "Default")
      (node (ref "EPD_C7") (pin "1") (pinfunction "1_1") (pintype "passive"))
      (node (ref "J1") (pin "19") (pinfunction "19_19") (pintype "bidirectional"))
    )
    (net (code "29") (name "Net-(EPD_C8-Pad1)") (class "Default")
      (node (ref "EPD_C8") (pin "1") (pinfunction "1_1") (pintype "passive"))
      (node (ref "J1") (pin "20") (pinfunction "20_20") (pintype "bidirectional"))
    )
    (net (code "30") (name "Net-(EPD_C10-Pad1)") (class "Default")
      (node (ref "EPD_C10") (pin "1") (pinfunction "1_1") (pintype "passive"))
      (node (ref "J1") (pin "22") (pinfunction "22_22") (pintype "bidirectional"))
    )
    (net (code "31") (name "Net-(EPD_C12-Pad1)") (class "Default")
      (node (ref "EPD_C12") (pin "1") (pinfunction "1_1") (pintype "passive"))
      (node (ref "J1") (pin "24") (pinfunction "24_24") (pintype "bidirectional"))
    )
    (net (code "32") (name "Net-(IC2-CT)") (class "Default")
      (node (ref "C_DELAY") (pin "1") (pinfunction "1_1") (pintype "passive"))
      (node (ref "IC2") (pin "5") (pinfunction "CT_5") (pintype "bidirectional"))
    )
    (net (code "33") (name "Net-(J2-PadA5)") (class "Default")
      (node (ref "J2") (pin "A5") (pinfunction "A5_A5") (pintype "bidirectional"))
      (node (ref "R2-USB1") (pin "1") (pinfunction "1_1") (pintype "passive"))
    )
    (net (code "34") (name "Net-(J2-PadB5)") (class "Default")
      (node (ref "J2") (pin "B5") (pinfunction "B5_B5") (pintype "bidirectional"))
      (node (ref "R2-USB2") (pin "2") (pinfunction "2_2") (pintype "passive"))
    )
    (net (code "35") (name "Net-(MCP73831-PROG)") (class "Default")
      (node (ref "MCP73831") (pin "5") (pinfunction "PROG_5") (pintype "input"))
      (node (ref "R2_BAT") (pin "2") (pinfunction "2_2") (pintype "passive"))
    )
    (net (code "36") (name "Net-(MCP73831-STAT)") (class "Default")
      (node (ref "MCP73831") (pin "1") (pinfunction "STAT_1") (pintype "output"))
      (node (ref "R1_BAT") (pin "1") (pinfunction "1_1") (pintype "passive"))
    )
    (net (code "37") (name "PREVGH") (class "Default")
      (node (ref "D5") (pin "1") (pinfunction "K_1") (pintype "bidirectional"))
      (node (ref "EPD_C9") (pin "1") (pinfunction "1_1") (pintype "passive"))
      (node (ref "J1") (pin "21") (pinfunction "21_21") (pintype "bidirectional"))
    )
    (net (code "38") (name "PREVGL") (class "Default")
      (node (ref "D4") (pin "2") (pinfunction "A_2") (pintype "bidirectional"))
      (node (ref "EPD_C11") (pin "1") (pinfunction "1_1") (pintype "passive"))
      (node (ref "J1") (pin "23") (pinfunction "23_23") (pintype "bidirectional"))
    )
    (net (code "39") (name "RESE") (class "Default")
      (node (ref "J1") (pin "3") (pinfunction "3_3") (pintype "bidirectional"))
      (node (ref "Q3") (pin "2") (pinfunction "S_2") (pintype "bidirectional"))
      (node (ref "R3") (pin "1") (pinfunction "1_1") (pintype "passive"))
    )
    (net (code "40") (name "RESE'") (class "Default")
      (node (ref "R2") (pin "2") (pinfunction "2_2") (pintype "passive"))
      (node (ref "R3") (pin "2") (pinfunction "2_2") (pintype "passive"))
      (node (ref "SJ1") (pin "2") (pinfunction "2_2") (pintype "passive"))
    )
    (net (code "41") (name "RESET") (class "Default")
      (node (ref "C5") (pin "1") (pinfunction "1_1") (pintype "passive"))
      (node (ref "IC2") (pin "1") (pinfunction "VOUT_1") (pintype "bidirectional"))
      (node (ref "RESET_BUTTIN") (pin "3") (pinfunction "3_3") (pintype "passive"))
      (node (ref "RESET_BUTTIN") (pin "4") (pinfunction "4_4") (pintype "passive"))
      (node (ref "R_RESET") (pin "2") (pinfunction "2_2") (pintype "passive"))
      (node (ref "U2") (pin "3") (pinfunction "EN_3") (pintype "input"))
    )
    (net (code "42") (name "RTC_RST") (class "Default")
      (node (ref "U2") (pin "16") (pinfunction "IO18_16") (pintype "bidirectional"))
      (node (ref "U3") (pin "4") (pinfunction "~{RST}_4") (pintype "input"))
    )
    (net (code "43") (name "RX") (class "Default")
      (node (ref "TP2") (pin "TP") (pinfunction "TP_TP") (pintype "input"))
      (node (ref "U2") (pin "24") (pinfunction "RXD0/GPIO17_24") (pintype "bidirectional"))
    )
    (net (code "44") (name "SCK") (class "Default")
      (node (ref "D10") (pin "1") (pinfunction "1_1") (pintype "passive"))
      (node (ref "J1") (pin "13") (pinfunction "13_13") (pintype "bidirectional"))
      (node (ref "J4") (pin "P5") (pinfunction "CLK_P5") (pintype "bidirectional"))
      (node (ref "R6") (pin "1") (pinfunction "1_1") (pintype "passive"))
      (node (ref "TP8") (pin "TP") (pinfunction "TP_TP") (pintype "input"))
      (node (ref "U1") (pin "6") (pinfunction "CLK_6") (pintype "input"))
      (node (ref "U2") (pin "6") (pinfunction "IO6_6") (pintype "bidirectional"))
    )
    (net (code "45") (name "SCL") (class "Default")
      (node (ref "J3") (pin "4") (pinfunction "4_4") (pintype "passive"))
      (node (ref "R2-PINH") (pin "1") (pinfunction "1_1") (pintype "passive"))
      (node (ref "SENSOR2") (pin "4") (pinfunction "SCK_4") (pintype "input"))
      (node (ref "U2") (pin "20") (pinfunction "IO22_20") (pintype "bidirectional"))
      (node (ref "U3") (pin "16") (pinfunction "SCL_16") (pintype "input"))
      (node (ref "U4") (pin "7") (pinfunction "SCL_7") (pintype "input"))
    )
    (net (code "46") (name "SDA") (class "Default")
      (node (ref "J3") (pin "3") (pinfunction "3_3") (pintype "passive"))
      (node (ref "R1-PINH") (pin "1") (pinfunction "1_1") (pintype "passive"))
      (node (ref "SENSOR2") (pin "3") (pinfunction "SDI_3") (pintype "bidirectional"))
      (node (ref "U2") (pin "19") (pinfunction "IO21_19") (pintype "bidirectional"))
      (node (ref "U3") (pin "15") (pinfunction "SDA_15") (pintype "bidirectional"))
      (node (ref "U4") (pin "8") (pinfunction "SDA_8") (pintype "bidirectional"))
    )
    (net (code "47") (name "SRC") (class "Default")
      (node (ref "C4") (pin "2") (pinfunction "2_2") (pintype "passive"))
      (node (ref "D5") (pin "2") (pinfunction "A_2") (pintype "bidirectional"))
      (node (ref "L1") (pin "1") (pinfunction "1_1") (pintype "passive"))
      (node (ref "Q3") (pin "3") (pinfunction "D_3") (pintype "bidirectional"))
    )
    (net (code "48") (name "SS_SD") (class "Default")
      (node (ref "D8") (pin "1") (pinfunction "1_1") (pintype "passive"))
      (node (ref "J4") (pin "P2") (pinfunction "CD/DAT3_P2") (pintype "bidirectional"))
      (node (ref "R10") (pin "1") (pinfunction "1_1") (pintype "passive"))
      (node (ref "U2") (pin "4") (pinfunction "IO4_4") (pintype "bidirectional"))
    )
    (net (code "49") (name "TX") (class "Default")
      (node (ref "TP1") (pin "TP") (pinfunction "TP_TP") (pintype "input"))
      (node (ref "U2") (pin "25") (pinfunction "TXD0/GPIO16_25") (pintype "bidirectional"))
    )
    (net (code "50") (name "USB_D+") (class "Default")
      (node (ref "D1") (pin "1") (pinfunction "I/O1_1_1") (pintype "bidirectional"))
      (node (ref "U2") (pin "14") (pinfunction "IO13_14") (pintype "bidirectional"))
    )
    (net (code "51") (name "USB_D-") (class "Default")
      (node (ref "D1") (pin "3") (pinfunction "I/O2_1_3") (pintype "bidirectional"))
      (node (ref "U2") (pin "13") (pinfunction "IO12_13") (pintype "bidirectional"))
    )
    (net (code "52") (name "VBAT") (class "Default")
      (node (ref "C2_BAT") (pin "1") (pinfunction "1_1") (pintype "passive"))
      (node (ref "MCP73831") (pin "3") (pinfunction "VBAT_3") (pintype "power_in"))
      (node (ref "Q1") (pin "3") (pinfunction "D_3") (pintype "bidirectional"))
      (node (ref "TP3") (pin "TP") (pinfunction "TP_TP") (pintype "input"))
      (node (ref "U4") (pin "2") (pinfunction "CELL_2") (pintype "power_in"))
      (node (ref "U4") (pin "3") (pinfunction "VDD_3") (pintype "power_in"))
    )
    (net (code "53") (name "VBUS") (class "Default")
      (node (ref "C1_BAT") (pin "1") (pinfunction "1_1") (pintype "passive"))
      (node (ref "C4_USB") (pin "2") (pinfunction "2_2") (pintype "passive"))
      (node (ref "C5_USB") (pin "2") (pinfunction "2_2") (pintype "passive"))
      (node (ref "CHG_LED") (pin "A") (pinfunction "A_A") (pintype "passive"))
      (node (ref "D1") (pin "5") (pinfunction "VBUS_5") (pintype "bidirectional"))
      (node (ref "D2") (pin "2") (pinfunction "ANODE_2") (pintype "bidirectional"))
      (node (ref "MCP73831") (pin "4") (pinfunction "VIN_4") (pintype "power_in"))
      (node (ref "PFMP.050.1") (pin "2") (pinfunction "2_2") (pintype "passive"))
      (node (ref "Q1") (pin "1") (pinfunction "G_1") (pintype "bidirectional"))
      (node (ref "R1_PWRUSB") (pin "2") (pinfunction "2_2") (pintype "passive"))
      (node (ref "TP14") (pin "TP") (pinfunction "TP_TP") (pintype "input"))
    )
    (net (code "54") (name "VRTC") (class "Default")
      (node (ref "C10_SUPERCAP") (pin "1") (pinfunction "1_1") (pintype "passive"))
      (node (ref "C8") (pin "1") (pinfunction "1_1") (pintype "passive"))
      (node (ref "R_CAPACITOR") (pin "2") (pinfunction "2_2") (pintype "passive"))
      (node (ref "U3") (pin "14") (pinfunction "VBAT_14") (pintype "power_in"))
    )
    (net (code "55") (name "VUSB") (class "Default")
      (node (ref "J2") (pin "A4") (pinfunction "A4_A4") (pintype "bidirectional"))
      (node (ref "J2") (pin "A9") (pinfunction "A9_A9") (pintype "bidirectional"))
      (node (ref "J2") (pin "B4") (pinfunction "B4_B4") (pintype "bidirectional"))
      (node (ref "J2") (pin "B9") (pinfunction "B9_B9") (pintype "bidirectional"))
      (node (ref "PFMP.050.1") (pin "1") (pinfunction "1_1") (pintype "passive"))
    )
    (net (code "56") (name "unconnected-(IC1-NC-Pad4)") (class "Default")
      (node (ref "IC1") (pin "4") (pinfunction "NC_4") (pintype "no_connect"))
    )
    (net (code "57") (name "unconnected-(IC2-NC-Pad4)") (class "Default")
      (node (ref "IC2") (pin "4") (pinfunction "NC_4") (pintype "no_connect"))
    )
    (net (code "58") (name "unconnected-(J1-Pad1)") (class "Default")
      (node (ref "J1") (pin "1") (pinfunction "1_1") (pintype "bidirectional"))
    )
    (net (code "59") (name "unconnected-(J1-Pad6)") (class "Default")
      (node (ref "J1") (pin "6") (pinfunction "6_6") (pintype "bidirectional"))
    )
    (net (code "60") (name "unconnected-(J1-Pad7)") (class "Default")
      (node (ref "J1") (pin "7") (pinfunction "7_7") (pintype "bidirectional"))
    )
    (net (code "61") (name "unconnected-(J2-PadA8)") (class "Default")
      (node (ref "J2") (pin "A8") (pinfunction "A8_A8") (pintype "bidirectional"))
    )
    (net (code "62") (name "unconnected-(J2-PadB8)") (class "Default")
      (node (ref "J2") (pin "B8") (pinfunction "B8_B8") (pintype "bidirectional"))
    )
    (net (code "63") (name "unconnected-(J4-DAT1-PadP8)") (class "Default")
      (node (ref "J4") (pin "P8") (pinfunction "DAT1_P8") (pintype "bidirectional"))
    )
    (net (code "64") (name "unconnected-(J4-DAT2-PadP1)") (class "Default")
      (node (ref "J4") (pin "P1") (pinfunction "DAT2_P1") (pintype "bidirectional"))
    )
    (net (code "65") (name "unconnected-(J4-DETECTION_1-PadS1)") (class "Default")
      (node (ref "J4") (pin "S1") (pinfunction "DETECTION_1_S1") (pintype "bidirectional"))
    )
    (net (code "66") (name "unconnected-(J4-DETECTION_2-PadS2)") (class "Default")
      (node (ref "J4") (pin "S2") (pinfunction "DETECTION_2_S2") (pintype "bidirectional"))
    )
    (net (code "67") (name "unconnected-(U2-NC-Pad22)") (class "Default")
      (node (ref "U2") (pin "22") (pinfunction "NC_22") (pintype "no_connect"))
    )
    (net (code "68") (name "unconnected-(U4-~{ALERT}-Pad5)") (class "Default")
      (node (ref "U4") (pin "5") (pinfunction "~{ALERT}_5") (pintype "output"))
    )
  )
)
